# AlarmClock.net
KiCad netlist of a schematic drawn in EAGLE
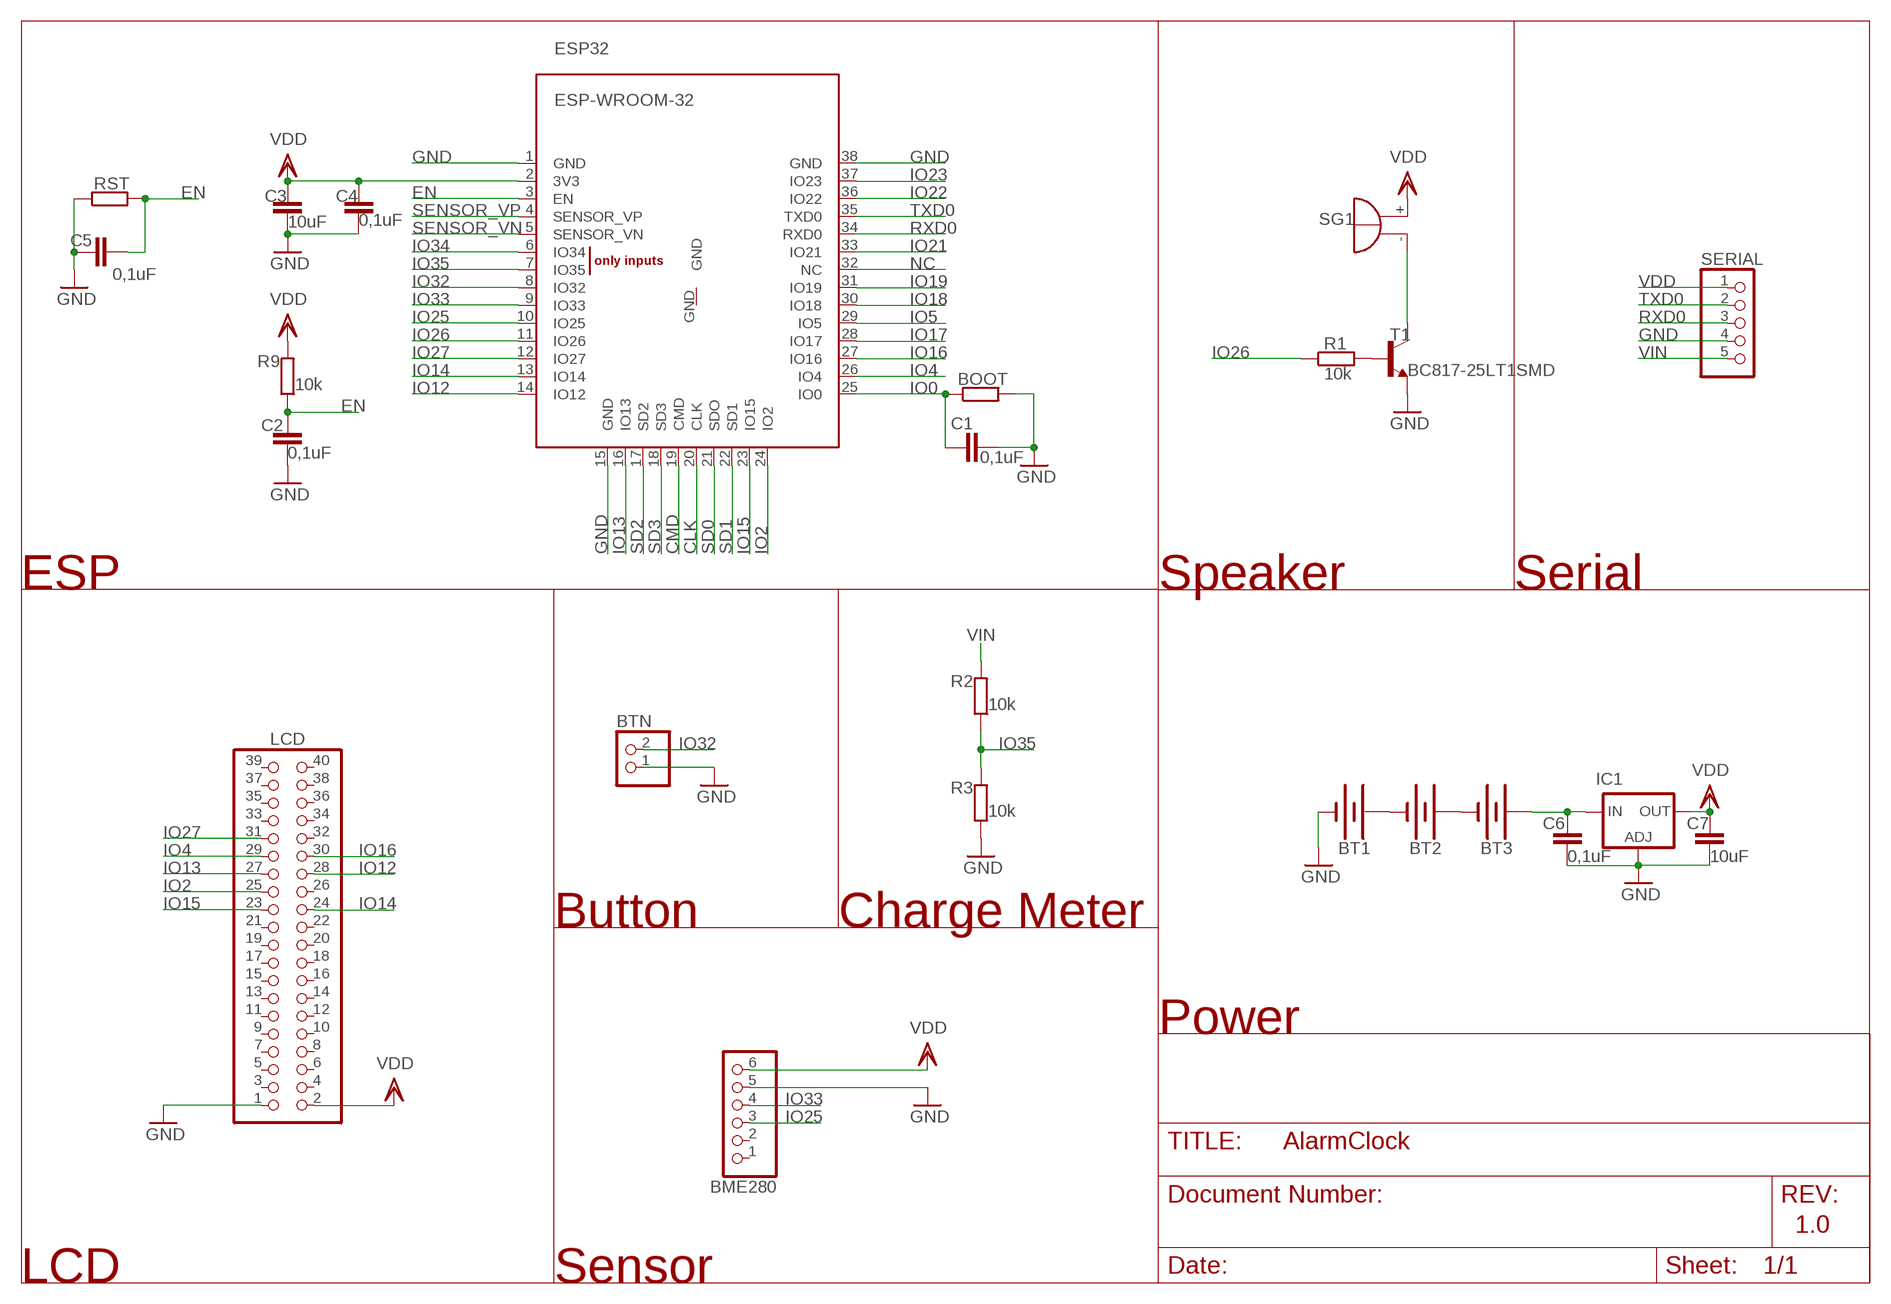
[diagram p0: schematic, sheet 1]

(export (version "E")
  (design (tool "Eeschema 10.0.6"))
  (components
    (comp (ref "BME280")
      (value "PINHD-1X6")
      (footprint "eagle-import:1X06")
      (libsource (lib "eagle-import") (part "PINHD-1X6"))
    )
    (comp (ref "BOOT")
      (value "R-EU_R1206")
      (footprint "eagle-import:R1206")
      (libsource (lib "eagle-import") (part "R-EU_R1206"))
    )
    (comp (ref "BT1")
      (value "HALTER1XUM4-LF")
      (footprint "eagle-import:HALTER1XUM4-LF")
      (libsource (lib "eagle-import") (part "HALTER1XUM4-LF"))
    )
    (comp (ref "BT2")
      (value "HALTER1XUM4-LF")
      (footprint "eagle-import:HALTER1XUM4-LF")
      (libsource (lib "eagle-import") (part "HALTER1XUM4-LF"))
    )
    (comp (ref "BT3")
      (value "HALTER1XUM4-LF")
      (footprint "eagle-import:HALTER1XUM4-LF")
      (libsource (lib "eagle-import") (part "HALTER1XUM4-LF"))
    )
    (comp (ref "BTN")
      (value "PINHD-1X2_2.54")
      (footprint "eagle-import:1X02")
      (libsource (lib "eagle-import") (part "PINHD-1X2_2.54"))
    )
    (comp (ref "C1")
      (value "0,1uF")
      (footprint "eagle-import:C1206")
      (libsource (lib "eagle-import") (part "C-EUC1206"))
    )
    (comp (ref "C2")
      (value "0,1uF")
      (footprint "eagle-import:C1206")
      (libsource (lib "eagle-import") (part "C-EUC1206"))
    )
    (comp (ref "C3")
      (value "10uF")
      (footprint "eagle-import:C1206")
      (libsource (lib "eagle-import") (part "C-EUC1206"))
    )
    (comp (ref "C4")
      (value "0,1uF")
      (footprint "eagle-import:C1206")
      (libsource (lib "eagle-import") (part "C-EUC1206"))
    )
    (comp (ref "C5")
      (value "0,1uF")
      (footprint "eagle-import:C1206")
      (libsource (lib "eagle-import") (part "C-EUC1206"))
    )
    (comp (ref "C6")
      (value "0,1uF")
      (footprint "eagle-import:C1206")
      (libsource (lib "eagle-import") (part "C-EUC1206"))
    )
    (comp (ref "C7")
      (value "10uF")
      (footprint "eagle-import:C1206")
      (libsource (lib "eagle-import") (part "C-EUC1206"))
    )
    (comp (ref "ESP32")
      (value "ESP-WROOM-32")
      (footprint "eagle-import:ESP-WROOM-32")
      (libsource (lib "eagle-import") (part "ESP-WROOM-32"))
    )
    (comp (ref "IC1")
      (value "LD1117AS33TR")
      (footprint "eagle-import:SOT223")
      (libsource (lib "eagle-import") (part "LD117A?S33TR"))
    )
    (comp (ref "LCD")
      (value "PINHD-2X20")
      (footprint "eagle-import:2X20")
      (libsource (lib "eagle-import") (part "PINHD-2X20"))
    )
    (comp (ref "R1")
      (value "10k")
      (footprint "eagle-import:R1206")
      (libsource (lib "eagle-import") (part "R-EU_R1206"))
    )
    (comp (ref "R2")
      (value "10k")
      (footprint "eagle-import:R1206")
      (libsource (lib "eagle-import") (part "R-EU_R1206"))
    )
    (comp (ref "R3")
      (value "10k")
      (footprint "eagle-import:R1206")
      (libsource (lib "eagle-import") (part "R-EU_R1206"))
    )
    (comp (ref "R9")
      (value "10k")
      (footprint "eagle-import:R1206")
      (libsource (lib "eagle-import") (part "R-EU_R1206"))
    )
    (comp (ref "RST")
      (value "R-EU_R1206")
      (footprint "eagle-import:R1206")
      (libsource (lib "eagle-import") (part "R-EU_R1206"))
    )
    (comp (ref "SERIAL")
      (value "PINHD-1X5_2.54-SMD-90°")
      (footprint "eagle-import:1X05SMD_90")
      (libsource (lib "eagle-import") (part "PINHD-1X5_2.54-SMD-90°"))
    )
    (comp (ref "SG1")
      (value "F/QMB")
      (footprint "eagle-import:F_QMB")
      (libsource (lib "eagle-import") (part "F/QMB"))
    )
    (comp (ref "T1")
      (value "BC817-25LT1SMD")
      (footprint "eagle-import:SOT23-BEC")
      (libsource (lib "eagle-import") (part "BC817SMD-25LT1"))
    )
  )
  (nets
    (net (code "1") (name "/CLK") (class "Default")
      (node (ref "ESP32") (pin "20") (pinfunction "CLK_20") (pintype "bidirectional"))
    )
    (net (code "2") (name "/CMD") (class "Default")
      (node (ref "ESP32") (pin "19") (pinfunction "CMD_19") (pintype "bidirectional"))
    )
    (net (code "3") (name "/EN") (class "Default")
      (node (ref "C2") (pin "2") (pinfunction "2_2") (pintype "passive"))
      (node (ref "C5") (pin "2") (pinfunction "2_2") (pintype "passive"))
      (node (ref "ESP32") (pin "3") (pinfunction "EN_3") (pintype "bidirectional"))
      (node (ref "R9") (pin "1") (pinfunction "1_1") (pintype "passive"))
      (node (ref "RST") (pin "2") (pinfunction "2_2") (pintype "passive"))
    )
    (net (code "4") (name "/IO0") (class "Default")
      (node (ref "BOOT") (pin "1") (pinfunction "1_1") (pintype "passive"))
      (node (ref "C1") (pin "2") (pinfunction "2_2") (pintype "passive"))
      (node (ref "ESP32") (pin "25") (pinfunction "IO0_25") (pintype "bidirectional"))
    )
    (net (code "5") (name "/IO2") (class "Default")
      (node (ref "ESP32") (pin "24") (pinfunction "IO2_24") (pintype "bidirectional"))
      (node (ref "LCD") (pin "25") (pinfunction "25_25") (pintype "passive"))
    )
    (net (code "6") (name "/IO4") (class "Default")
      (node (ref "ESP32") (pin "26") (pinfunction "IO4_26") (pintype "bidirectional"))
      (node (ref "LCD") (pin "29") (pinfunction "29_29") (pintype "passive"))
    )
    (net (code "7") (name "/IO5") (class "Default")
      (node (ref "ESP32") (pin "29") (pinfunction "IO5_29") (pintype "bidirectional"))
    )
    (net (code "8") (name "/IO12") (class "Default")
      (node (ref "ESP32") (pin "14") (pinfunction "IO12_14") (pintype "bidirectional"))
      (node (ref "LCD") (pin "28") (pinfunction "28_28") (pintype "passive"))
    )
    (net (code "9") (name "/IO13") (class "Default")
      (node (ref "ESP32") (pin "16") (pinfunction "IO13_16") (pintype "bidirectional"))
      (node (ref "LCD") (pin "27") (pinfunction "27_27") (pintype "passive"))
    )
    (net (code "10") (name "/IO14") (class "Default")
      (node (ref "ESP32") (pin "13") (pinfunction "IO14_13") (pintype "bidirectional"))
      (node (ref "LCD") (pin "24") (pinfunction "24_24") (pintype "passive"))
    )
    (net (code "11") (name "/IO15") (class "Default")
      (node (ref "ESP32") (pin "23") (pinfunction "IO15_23") (pintype "bidirectional"))
      (node (ref "LCD") (pin "23") (pinfunction "23_23") (pintype "passive"))
    )
    (net (code "12") (name "/IO16") (class "Default")
      (node (ref "ESP32") (pin "27") (pinfunction "IO16_27") (pintype "bidirectional"))
      (node (ref "LCD") (pin "30") (pinfunction "30_30") (pintype "passive"))
    )
    (net (code "13") (name "/IO17") (class "Default")
      (node (ref "ESP32") (pin "28") (pinfunction "IO17_28") (pintype "bidirectional"))
    )
    (net (code "14") (name "/IO18") (class "Default")
      (node (ref "ESP32") (pin "30") (pinfunction "IO18_30") (pintype "bidirectional"))
    )
    (net (code "15") (name "/IO19") (class "Default")
      (node (ref "ESP32") (pin "31") (pinfunction "IO19_31") (pintype "bidirectional"))
    )
    (net (code "16") (name "/IO21") (class "Default")
      (node (ref "ESP32") (pin "33") (pinfunction "IO21_33") (pintype "bidirectional"))
    )
    (net (code "17") (name "/IO22") (class "Default")
      (node (ref "ESP32") (pin "36") (pinfunction "IO22_36") (pintype "bidirectional"))
    )
    (net (code "18") (name "/IO23") (class "Default")
      (node (ref "ESP32") (pin "37") (pinfunction "IO23_37") (pintype "bidirectional"))
    )
    (net (code "19") (name "/IO25") (class "Default")
      (node (ref "BME280") (pin "3") (pinfunction "3_3") (pintype "passive"))
      (node (ref "ESP32") (pin "10") (pinfunction "IO25_10") (pintype "bidirectional"))
    )
    (net (code "20") (name "/IO26") (class "Default")
      (node (ref "ESP32") (pin "11") (pinfunction "IO26_11") (pintype "bidirectional"))
      (node (ref "R1") (pin "1") (pinfunction "1_1") (pintype "passive"))
    )
    (net (code "21") (name "/IO27") (class "Default")
      (node (ref "ESP32") (pin "12") (pinfunction "IO27_12") (pintype "bidirectional"))
      (node (ref "LCD") (pin "31") (pinfunction "31_31") (pintype "passive"))
    )
    (net (code "22") (name "/IO32") (class "Default")
      (node (ref "BTN") (pin "2") (pinfunction "2_2") (pintype "passive"))
      (node (ref "ESP32") (pin "8") (pinfunction "IO32_8") (pintype "bidirectional"))
    )
    (net (code "23") (name "/IO33") (class "Default")
      (node (ref "BME280") (pin "4") (pinfunction "4_4") (pintype "passive"))
      (node (ref "ESP32") (pin "9") (pinfunction "IO33_9") (pintype "bidirectional"))
    )
    (net (code "24") (name "/IO34") (class "Default")
      (node (ref "ESP32") (pin "6") (pinfunction "IO34_6") (pintype "input"))
    )
    (net (code "25") (name "/IO35") (class "Default")
      (node (ref "ESP32") (pin "7") (pinfunction "IO35_7") (pintype "input"))
      (node (ref "R2") (pin "1") (pinfunction "1_1") (pintype "passive"))
      (node (ref "R3") (pin "2") (pinfunction "2_2") (pintype "passive"))
    )
    (net (code "26") (name "/NC") (class "Default")
      (node (ref "ESP32") (pin "32") (pinfunction "NC_32") (pintype "bidirectional"))
    )
    (net (code "27") (name "/RXD0") (class "Default")
      (node (ref "ESP32") (pin "34") (pinfunction "RXD0_34") (pintype "bidirectional"))
      (node (ref "SERIAL") (pin "3") (pinfunction "3_3") (pintype "passive"))
    )
    (net (code "28") (name "/SD0") (class "Default")
      (node (ref "ESP32") (pin "21") (pinfunction "SDO_21") (pintype "bidirectional"))
    )
    (net (code "29") (name "/SD1") (class "Default")
      (node (ref "ESP32") (pin "22") (pinfunction "SD1_22") (pintype "bidirectional"))
    )
    (net (code "30") (name "/SD2") (class "Default")
      (node (ref "ESP32") (pin "17") (pinfunction "SD2_17") (pintype "bidirectional"))
    )
    (net (code "31") (name "/SD3") (class "Default")
      (node (ref "ESP32") (pin "18") (pinfunction "SD3_18") (pintype "bidirectional"))
    )
    (net (code "32") (name "/SENSOR_VN") (class "Default")
      (node (ref "ESP32") (pin "5") (pinfunction "SENSOR_VN_5") (pintype "input"))
    )
    (net (code "33") (name "/SENSOR_VP") (class "Default")
      (node (ref "ESP32") (pin "4") (pinfunction "SENSOR_VP_4") (pintype "input"))
    )
    (net (code "34") (name "/TXD0") (class "Default")
      (node (ref "ESP32") (pin "35") (pinfunction "TXD0_35") (pintype "bidirectional"))
      (node (ref "SERIAL") (pin "2") (pinfunction "2_2") (pintype "passive"))
    )
    (net (code "35") (name "/VIN") (class "Default")
      (node (ref "BT3") (pin "P$1") (pinfunction "+_P$1") (pintype "power_in"))
      (node (ref "C6") (pin "2") (pinfunction "2_2") (pintype "passive"))
      (node (ref "IC1") (pin "3") (pinfunction "IN_3") (pintype "input"))
      (node (ref "R2") (pin "2") (pinfunction "2_2") (pintype "passive"))
      (node (ref "SERIAL") (pin "5") (pinfunction "5_5") (pintype "passive"))
    )
    (net (code "36") (name "GND") (class "Default")
      (node (ref "BME280") (pin "5") (pinfunction "5_5") (pintype "passive"))
      (node (ref "BOOT") (pin "2") (pinfunction "2_2") (pintype "passive"))
      (node (ref "BT1") (pin "P$2") (pinfunction "-_P$2") (pintype "power_in"))
      (node (ref "BTN") (pin "1") (pinfunction "1_1") (pintype "passive"))
      (node (ref "C1") (pin "1") (pinfunction "1_1") (pintype "passive"))
      (node (ref "C2") (pin "1") (pinfunction "1_1") (pintype "passive"))
      (node (ref "C3") (pin "1") (pinfunction "1_1") (pintype "passive"))
      (node (ref "C4") (pin "1") (pinfunction "1_1") (pintype "passive"))
      (node (ref "C5") (pin "1") (pinfunction "1_1") (pintype "passive"))
      (node (ref "C6") (pin "1") (pinfunction "1_1") (pintype "passive"))
      (node (ref "C7") (pin "1") (pinfunction "1_1") (pintype "passive"))
      (node (ref "ESP32") (pin "1") (pinfunction "GND_1") (pintype "bidirectional"))
      (node (ref "ESP32") (pin "15") (pinfunction "GND_15") (pintype "bidirectional"))
      (node (ref "ESP32") (pin "38") (pinfunction "GND_38") (pintype "bidirectional"))
      (node (ref "IC1") (pin "1") (pinfunction "ADJ_1") (pintype "input"))
      (node (ref "LCD") (pin "1") (pinfunction "1_1") (pintype "passive"))
      (node (ref "R3") (pin "1") (pinfunction "1_1") (pintype "passive"))
      (node (ref "RST") (pin "1") (pinfunction "1_1") (pintype "passive"))
      (node (ref "SERIAL") (pin "4") (pinfunction "4_4") (pintype "passive"))
      (node (ref "T1") (pin "E") (pinfunction "E_E") (pintype "passive"))
    )
    (net (code "37") (name "Net-(BT1-+)") (class "Default")
      (node (ref "BT1") (pin "P$1") (pinfunction "+_P$1") (pintype "power_in"))
      (node (ref "BT2") (pin "P$2") (pinfunction "-_P$2") (pintype "power_in"))
    )
    (net (code "38") (name "Net-(BT2-+)") (class "Default")
      (node (ref "BT2") (pin "P$1") (pinfunction "+_P$1") (pintype "power_in"))
      (node (ref "BT3") (pin "P$2") (pinfunction "-_P$2") (pintype "power_in"))
    )
    (net (code "39") (name "Net-(R1-Pad2)") (class "Default")
      (node (ref "R1") (pin "2") (pinfunction "2_2") (pintype "passive"))
      (node (ref "T1") (pin "B") (pinfunction "B_B") (pintype "passive"))
    )
    (net (code "40") (name "Net-(SG1-+)") (class "Default")
      (node (ref "SG1") (pin "-") (pinfunction "+_-") (pintype "passive"))
      (node (ref "T1") (pin "C") (pinfunction "C_C") (pintype "passive"))
    )
    (net (code "41") (name "VDD") (class "Default")
      (node (ref "BME280") (pin "6") (pinfunction "6_6") (pintype "passive"))
      (node (ref "C3") (pin "2") (pinfunction "2_2") (pintype "passive"))
      (node (ref "C4") (pin "2") (pinfunction "2_2") (pintype "passive"))
      (node (ref "C7") (pin "2") (pinfunction "2_2") (pintype "passive"))
      (node (ref "ESP32") (pin "2") (pinfunction "3V3_2") (pintype "bidirectional"))
      (node (ref "IC1") (pin "4") (pinfunction "OUT_4") (pintype "passive"))
      (node (ref "LCD") (pin "2") (pinfunction "2_2") (pintype "passive"))
      (node (ref "R9") (pin "2") (pinfunction "2_2") (pintype "passive"))
      (node (ref "SERIAL") (pin "1") (pinfunction "1_1") (pintype "passive"))
      (node (ref "SG1") (pin "+") (pinfunction "-_+") (pintype "passive"))
    )
    (net (code "42") (name "unconnected-(BME280-Pad1)") (class "Default")
      (node (ref "BME280") (pin "1") (pinfunction "1_1") (pintype "passive"))
    )
    (net (code "43") (name "unconnected-(BME280-Pad2)") (class "Default")
      (node (ref "BME280") (pin "2") (pinfunction "2_2") (pintype "passive"))
    )
    (net (code "44") (name "unconnected-(ESP32-PadGND)") (class "Default")
      (node (ref "ESP32") (pin "GND") (pinfunction "GND_GND") (pintype "bidirectional"))
    )
    (net (code "45") (name "unconnected-(LCD-Pad3)") (class "Default")
      (node (ref "LCD") (pin "3") (pinfunction "3_3") (pintype "passive"))
    )
    (net (code "46") (name "unconnected-(LCD-Pad4)") (class "Default")
      (node (ref "LCD") (pin "4") (pinfunction "4_4") (pintype "passive"))
    )
    (net (code "47") (name "unconnected-(LCD-Pad5)") (class "Default")
      (node (ref "LCD") (pin "5") (pinfunction "5_5") (pintype "passive"))
    )
    (net (code "48") (name "unconnected-(LCD-Pad6)") (class "Default")
      (node (ref "LCD") (pin "6") (pinfunction "6_6") (pintype "passive"))
    )
    (net (code "49") (name "unconnected-(LCD-Pad7)") (class "Default")
      (node (ref "LCD") (pin "7") (pinfunction "7_7") (pintype "passive"))
    )
    (net (code "50") (name "unconnected-(LCD-Pad8)") (class "Default")
      (node (ref "LCD") (pin "8") (pinfunction "8_8") (pintype "passive"))
    )
    (net (code "51") (name "unconnected-(LCD-Pad9)") (class "Default")
      (node (ref "LCD") (pin "9") (pinfunction "9_9") (pintype "passive"))
    )
    (net (code "52") (name "unconnected-(LCD-Pad10)") (class "Default")
      (node (ref "LCD") (pin "10") (pinfunction "10_10") (pintype "passive"))
    )
    (net (code "53") (name "unconnected-(LCD-Pad11)") (class "Default")
      (node (ref "LCD") (pin "11") (pinfunction "11_11") (pintype "passive"))
    )
    (net (code "54") (name "unconnected-(LCD-Pad12)") (class "Default")
      (node (ref "LCD") (pin "12") (pinfunction "12_12") (pintype "passive"))
    )
    (net (code "55") (name "unconnected-(LCD-Pad13)") (class "Default")
      (node (ref "LCD") (pin "13") (pinfunction "13_13") (pintype "passive"))
    )
    (net (code "56") (name "unconnected-(LCD-Pad14)") (class "Default")
      (node (ref "LCD") (pin "14") (pinfunction "14_14") (pintype "passive"))
    )
    (net (code "57") (name "unconnected-(LCD-Pad15)") (class "Default")
      (node (ref "LCD") (pin "15") (pinfunction "15_15") (pintype "passive"))
    )
    (net (code "58") (name "unconnected-(LCD-Pad16)") (class "Default")
      (node (ref "LCD") (pin "16") (pinfunction "16_16") (pintype "passive"))
    )
    (net (code "59") (name "unconnected-(LCD-Pad17)") (class "Default")
      (node (ref "LCD") (pin "17") (pinfunction "17_17") (pintype "passive"))
    )
    (net (code "60") (name "unconnected-(LCD-Pad18)") (class "Default")
      (node (ref "LCD") (pin "18") (pinfunction "18_18") (pintype "passive"))
    )
    (net (code "61") (name "unconnected-(LCD-Pad19)") (class "Default")
      (node (ref "LCD") (pin "19") (pinfunction "19_19") (pintype "passive"))
    )
    (net (code "62") (name "unconnected-(LCD-Pad20)") (class "Default")
      (node (ref "LCD") (pin "20") (pinfunction "20_20") (pintype "passive"))
    )
    (net (code "63") (name "unconnected-(LCD-Pad21)") (class "Default")
      (node (ref "LCD") (pin "21") (pinfunction "21_21") (pintype "passive"))
    )
    (net (code "64") (name "unconnected-(LCD-Pad22)") (class "Default")
      (node (ref "LCD") (pin "22") (pinfunction "22_22") (pintype "passive"))
    )
    (net (code "65") (name "unconnected-(LCD-Pad26)") (class "Default")
      (node (ref "LCD") (pin "26") (pinfunction "26_26") (pintype "passive"))
    )
    (net (code "66") (name "unconnected-(LCD-Pad32)") (class "Default")
      (node (ref "LCD") (pin "32") (pinfunction "32_32") (pintype "passive"))
    )
    (net (code "67") (name "unconnected-(LCD-Pad33)") (class "Default")
      (node (ref "LCD") (pin "33") (pinfunction "33_33") (pintype "passive"))
    )
    (net (code "68") (name "unconnected-(LCD-Pad34)") (class "Default")
      (node (ref "LCD") (pin "34") (pinfunction "34_34") (pintype "passive"))
    )
    (net (code "69") (name "unconnected-(LCD-Pad35)") (class "Default")
      (node (ref "LCD") (pin "35") (pinfunction "35_35") (pintype "passive"))
    )
    (net (code "70") (name "unconnected-(LCD-Pad36)") (class "Default")
      (node (ref "LCD") (pin "36") (pinfunction "36_36") (pintype "passive"))
    )
    (net (code "71") (name "unconnected-(LCD-Pad37)") (class "Default")
      (node (ref "LCD") (pin "37") (pinfunction "37_37") (pintype "passive"))
    )
    (net (code "72") (name "unconnected-(LCD-Pad38)") (class "Default")
      (node (ref "LCD") (pin "38") (pinfunction "38_38") (pintype "passive"))
    )
    (net (code "73") (name "unconnected-(LCD-Pad39)") (class "Default")
      (node (ref "LCD") (pin "39") (pinfunction "39_39") (pintype "passive"))
    )
    (net (code "74") (name "unconnected-(LCD-Pad40)") (class "Default")
      (node (ref "LCD") (pin "40") (pinfunction "40_40") (pintype "passive"))
    )
  )
)
